# Adafruit_NeoKey_CHOC_Socket_Breakout.net
KiCad netlist of a schematic drawn in EAGLE
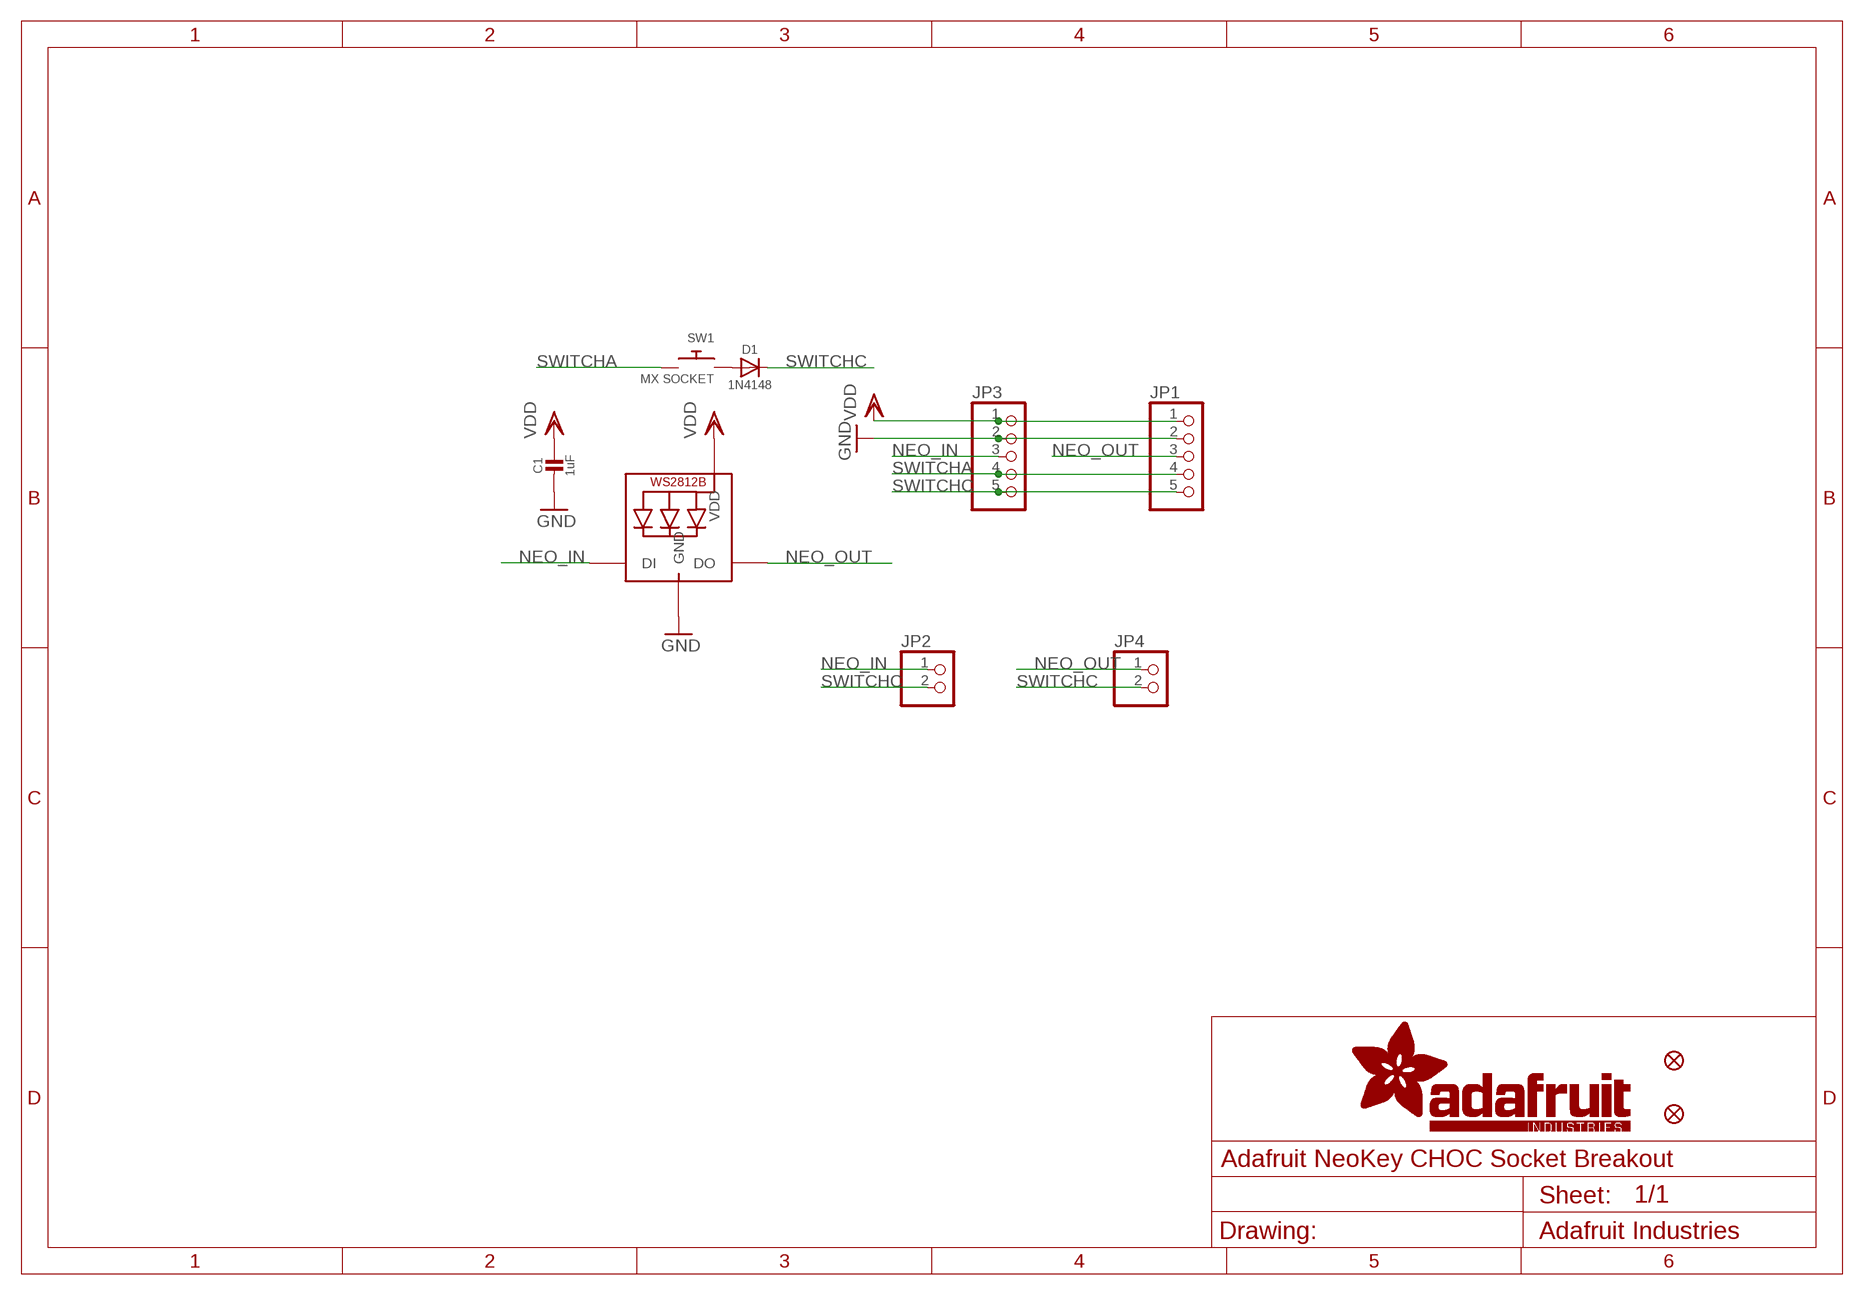
[diagram p0: schematic, sheet 1]

(export (version "E")
  (design (tool "Eeschema 10.0.6"))
  (components
    (comp (ref "C1")
      (value "1uF")
      (footprint "eagle-import:0603-NO")
      (libsource (lib "eagle-import") (part "CAP_CERAMIC0603_NO"))
    )
    (comp (ref "D1")
      (value "1N4148")
      (footprint "eagle-import:SOD-323")
      (libsource (lib "eagle-import") (part "DIODESOD-323"))
    )
    (comp (ref "FID3")
      (value "FIDUCIAL_1MM")
      (footprint "eagle-import:FIDUCIAL_1MM")
      (libsource (lib "eagle-import") (part "FIDUCIAL_1MM"))
    )
    (comp (ref "FID4")
      (value "FIDUCIAL_1MM")
      (footprint "eagle-import:FIDUCIAL_1MM")
      (libsource (lib "eagle-import") (part "FIDUCIAL_1MM"))
    )
    (comp (ref "JP1")
      (value "HEADER-1X570MIL")
      (footprint "eagle-import:1X05_ROUND_70")
      (libsource (lib "eagle-import") (part "HEADER-1X570MIL"))
    )
    (comp (ref "JP2")
      (value "HEADER-1X2ROUND")
      (footprint "eagle-import:1X02_ROUND")
      (libsource (lib "eagle-import") (part "HEADER-1X2ROUND"))
    )
    (comp (ref "JP3")
      (value "HEADER-1X570MIL")
      (footprint "eagle-import:1X05_ROUND_70")
      (libsource (lib "eagle-import") (part "HEADER-1X570MIL"))
    )
    (comp (ref "JP4")
      (value "HEADER-1X2ROUND")
      (footprint "eagle-import:1X02_ROUND")
      (libsource (lib "eagle-import") (part "HEADER-1X2ROUND"))
    )
    (comp (ref "LED1")
      (value "WS2812B_SK6812E")
      (footprint "eagle-import:NEO3535_REVERSE")
      (libsource (lib "eagle-import") (part "WS2812B_SK6812E"))
    )
    (comp (ref "SW1")
      (value "MX SOCKET")
      (footprint "eagle-import:KAILH_CHOC_SOCKET")
      (libsource (lib "eagle-import") (part "SWITCH_PUSHBUTTON_CHOCSOCKET"))
    )
  )
  (nets
    (net (code "1") (name "/NEO_IN") (class "Default")
      (node (ref "JP2") (pin "1") (pinfunction "1_1") (pintype "passive"))
      (node (ref "JP3") (pin "3") (pinfunction "3_3") (pintype "passive"))
      (node (ref "LED1") (pin "4-DIN") (pinfunction "DI_4-DIN") (pintype "input"))
    )
    (net (code "2") (name "/NEO_OUT") (class "Default")
      (node (ref "JP1") (pin "3") (pinfunction "3_3") (pintype "passive"))
      (node (ref "JP4") (pin "1") (pinfunction "1_1") (pintype "passive"))
      (node (ref "LED1") (pin "2-DOUT") (pinfunction "DO_2-DOUT") (pintype "output"))
    )
    (net (code "3") (name "/SWITCHA") (class "Default")
      (node (ref "JP1") (pin "4") (pinfunction "4_4") (pintype "passive"))
      (node (ref "JP3") (pin "4") (pinfunction "4_4") (pintype "passive"))
      (node (ref "SW1") (pin "2") (pinfunction "P$2_2") (pintype "passive"))
    )
    (net (code "4") (name "/SWITCHC") (class "Default")
      (node (ref "D1") (pin "C") (pinfunction "C_C") (pintype "passive"))
      (node (ref "JP1") (pin "5") (pinfunction "5_5") (pintype "passive"))
      (node (ref "JP2") (pin "2") (pinfunction "2_2") (pintype "passive"))
      (node (ref "JP3") (pin "5") (pinfunction "5_5") (pintype "passive"))
      (node (ref "JP4") (pin "2") (pinfunction "2_2") (pintype "passive"))
    )
    (net (code "5") (name "GND") (class "Default")
      (node (ref "C1") (pin "2") (pinfunction "2_2") (pintype "passive"))
      (node (ref "JP1") (pin "2") (pinfunction "2_2") (pintype "passive"))
      (node (ref "JP3") (pin "2") (pinfunction "2_2") (pintype "passive"))
      (node (ref "LED1") (pin "3-GND") (pinfunction "GND_3-GND") (pintype "power_in"))
    )
    (net (code "6") (name "Net-(SW1-P$1)") (class "Default")
      (node (ref "D1") (pin "A") (pinfunction "A_A") (pintype "passive"))
      (node (ref "SW1") (pin "1") (pinfunction "P$1_1") (pintype "passive"))
    )
    (net (code "7") (name "VDD") (class "Default")
      (node (ref "C1") (pin "1") (pinfunction "1_1") (pintype "passive"))
      (node (ref "JP1") (pin "1") (pinfunction "1_1") (pintype "passive"))
      (node (ref "JP3") (pin "1") (pinfunction "1_1") (pintype "passive"))
      (node (ref "LED1") (pin "1-VDD") (pinfunction "VDD_1-VDD") (pintype "power_in"))
    )
  )
)
